# progESP.net
KiCad netlist of a schematic drawn in EAGLE
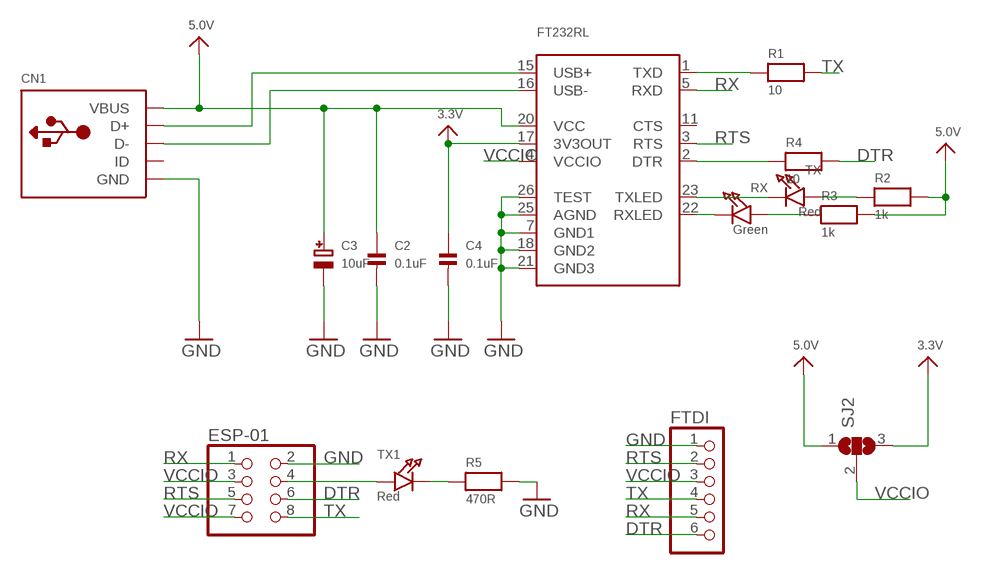
[diagram p0: schematic, sheet 1]

(export (version "E")
  (design (tool "Eeschema 10.0.6"))
  (components
    (comp (ref "C2")
      (value "0.1uF")
      (footprint "eagle-import:0805")
      (libsource (lib "eagle-import") (part "CAP_CERAMIC0805"))
    )
    (comp (ref "C3")
      (value "10uF")
      (footprint "eagle-import:EIA3216-18_A-R")
      (libsource (lib "eagle-import") (part "CAP_TANTALUMA/3216_REFLOW"))
    )
    (comp (ref "C4")
      (value "0.1uF")
      (footprint "eagle-import:0805")
      (libsource (lib "eagle-import") (part "CAP_CERAMIC0805"))
    )
    (comp (ref "CN1")
      (value "USBMINIB")
      (footprint "eagle-import:USB-MINIB")
      (libsource (lib "eagle-import") (part "USBMINIB"))
    )
    (comp (ref "ESP-01")
      (value "PINHD-2X4-ESP-01")
      (footprint "eagle-import:2X04")
      (libsource (lib "eagle-import") (part "PINHD-2X4-ESP-01"))
    )
    (comp (ref "FT232RL")
      (value "FT232RLSSOP28")
      (footprint "eagle-import:SSOP28DB")
      (libsource (lib "eagle-import") (part "FT232RLSSOP28"))
    )
    (comp (ref "FTDI")
      (value "PINHD-1X6")
      (footprint "eagle-import:1X06")
      (libsource (lib "eagle-import") (part "PINHD-1X6"))
    )
    (comp (ref "R1")
      (value "10")
      (footprint "eagle-import:0805")
      (libsource (lib "eagle-import") (part "RESISTOR0805"))
    )
    (comp (ref "R2")
      (value "1k")
      (footprint "eagle-import:0805")
      (libsource (lib "eagle-import") (part "RESISTOR0805"))
    )
    (comp (ref "R3")
      (value "1k")
      (footprint "eagle-import:0805")
      (libsource (lib "eagle-import") (part "RESISTOR0805"))
    )
    (comp (ref "R4")
      (value "10")
      (footprint "eagle-import:0805")
      (libsource (lib "eagle-import") (part "RESISTOR0805"))
    )
    (comp (ref "R5")
      (value "470R")
      (footprint "eagle-import:0805")
      (libsource (lib "eagle-import") (part "RESISTOR0805"))
    )
    (comp (ref "RX")
      (value "Green")
      (footprint "eagle-import:CHIPLED_0805")
      (libsource (lib "eagle-import") (part "LED0805"))
    )
    (comp (ref "SJ2")
      (value "SJ2W")
      (footprint "eagle-import:SJ_2")
      (libsource (lib "eagle-import") (part "SJ2W"))
    )
    (comp (ref "TX")
      (value "Red")
      (footprint "eagle-import:CHIPLED_0805")
      (libsource (lib "eagle-import") (part "LED0805"))
    )
    (comp (ref "TX1")
      (value "Red")
      (footprint "eagle-import:CHIPLED_0805")
      (libsource (lib "eagle-import") (part "LED0805"))
    )
  )
  (nets
    (net (code "1") (name "/DTR") (class "Default")
      (node (ref "ESP-01") (pin "6") (pinfunction "6_6") (pintype "passive"))
      (node (ref "FTDI") (pin "6") (pinfunction "6_6") (pintype "passive"))
      (node (ref "R4") (pin "2") (pinfunction "2_2") (pintype "passive"))
    )
    (net (code "2") (name "/RTS") (class "Default")
      (node (ref "ESP-01") (pin "5") (pinfunction "5_5") (pintype "passive"))
      (node (ref "FT232RL") (pin "3") (pinfunction "RTS_3") (pintype "bidirectional"))
      (node (ref "FTDI") (pin "2") (pinfunction "2_2") (pintype "passive"))
    )
    (net (code "3") (name "/RX") (class "Default")
      (node (ref "ESP-01") (pin "1") (pinfunction "1_1") (pintype "passive"))
      (node (ref "FT232RL") (pin "5") (pinfunction "RXD_5") (pintype "input"))
      (node (ref "FTDI") (pin "5") (pinfunction "5_5") (pintype "passive"))
    )
    (net (code "4") (name "/TX") (class "Default")
      (node (ref "ESP-01") (pin "8") (pinfunction "8_8") (pintype "passive"))
      (node (ref "FTDI") (pin "4") (pinfunction "4_4") (pintype "passive"))
      (node (ref "R1") (pin "2") (pinfunction "2_2") (pintype "passive"))
    )
    (net (code "5") (name "/VCCIO") (class "Default")
      (node (ref "ESP-01") (pin "3") (pinfunction "3_3") (pintype "passive"))
      (node (ref "ESP-01") (pin "7") (pinfunction "7_7") (pintype "passive"))
      (node (ref "FT232RL") (pin "4") (pinfunction "VCCIO_4") (pintype "power_in"))
      (node (ref "FTDI") (pin "3") (pinfunction "3_3") (pintype "passive"))
      (node (ref "SJ2") (pin "2") (pinfunction "2_2") (pintype "passive"))
    )
    (net (code "6") (name "3.3V") (class "Default")
      (node (ref "C4") (pin "1") (pinfunction "P$1_1") (pintype "passive"))
      (node (ref "FT232RL") (pin "17") (pinfunction "3V3OUT_17") (pintype "power_in"))
      (node (ref "SJ2") (pin "3") (pinfunction "3_3") (pintype "passive"))
    )
    (net (code "7") (name "5.0V") (class "Default")
      (node (ref "C2") (pin "1") (pinfunction "P$1_1") (pintype "passive"))
      (node (ref "C3") (pin "+") (pinfunction "+_+") (pintype "passive"))
      (node (ref "CN1") (pin "VBUS") (pinfunction "VBUS_VBUS") (pintype "power_in"))
      (node (ref "FT232RL") (pin "20") (pinfunction "VCC_20") (pintype "power_in"))
      (node (ref "R2") (pin "2") (pinfunction "2_2") (pintype "passive"))
      (node (ref "R3") (pin "2") (pinfunction "2_2") (pintype "passive"))
      (node (ref "SJ2") (pin "1") (pinfunction "1_1") (pintype "passive"))
    )
    (net (code "8") (name "GND") (class "Default")
      (node (ref "C2") (pin "2") (pinfunction "P$2_2") (pintype "passive"))
      (node (ref "C3") (pin "-") (pinfunction "-_-") (pintype "passive"))
      (node (ref "C4") (pin "2") (pinfunction "P$2_2") (pintype "passive"))
      (node (ref "CN1") (pin "GND") (pinfunction "GND_GND") (pintype "power_in"))
      (node (ref "ESP-01") (pin "2") (pinfunction "2_2") (pintype "passive"))
      (node (ref "FT232RL") (pin "18") (pinfunction "GND2_18") (pintype "power_in"))
      (node (ref "FT232RL") (pin "21") (pinfunction "GND3_21") (pintype "power_in"))
      (node (ref "FT232RL") (pin "25") (pinfunction "AGND_25") (pintype "power_in"))
      (node (ref "FT232RL") (pin "26") (pinfunction "TEST_26") (pintype "input"))
      (node (ref "FT232RL") (pin "7") (pinfunction "GND1_7") (pintype "power_in"))
      (node (ref "FTDI") (pin "1") (pinfunction "1_1") (pintype "passive"))
      (node (ref "R5") (pin "2") (pinfunction "2_2") (pintype "passive"))
    )
    (net (code "9") (name "Net-(ESP-01-Pad4)") (class "Default")
      (node (ref "ESP-01") (pin "4") (pinfunction "4_4") (pintype "passive"))
      (node (ref "TX1") (pin "A") (pinfunction "A_A") (pintype "passive"))
    )
    (net (code "10") (name "Net-(FT232RL-DTR)") (class "Default")
      (node (ref "FT232RL") (pin "2") (pinfunction "DTR_2") (pintype "bidirectional"))
      (node (ref "R4") (pin "1") (pinfunction "1_1") (pintype "passive"))
    )
    (net (code "11") (name "Net-(FT232RL-RXLED)") (class "Default")
      (node (ref "FT232RL") (pin "22") (pinfunction "RXLED_22") (pintype "bidirectional"))
      (node (ref "RX") (pin "C") (pinfunction "C_C") (pintype "passive"))
    )
    (net (code "12") (name "Net-(FT232RL-TXD)") (class "Default")
      (node (ref "FT232RL") (pin "1") (pinfunction "TXD_1") (pintype "output"))
      (node (ref "R1") (pin "1") (pinfunction "1_1") (pintype "passive"))
    )
    (net (code "13") (name "Net-(FT232RL-TXLED)") (class "Default")
      (node (ref "FT232RL") (pin "23") (pinfunction "TXLED_23") (pintype "bidirectional"))
      (node (ref "TX") (pin "C") (pinfunction "C_C") (pintype "passive"))
    )
    (net (code "14") (name "Net-(FT232RL-USB+)") (class "Default")
      (node (ref "CN1") (pin "D+") (pinfunction "D+_D+") (pintype "bidirectional"))
      (node (ref "FT232RL") (pin "15") (pinfunction "USB+_15") (pintype "bidirectional"))
    )
    (net (code "15") (name "Net-(FT232RL-USB-)") (class "Default")
      (node (ref "CN1") (pin "D-") (pinfunction "D-_D-") (pintype "bidirectional"))
      (node (ref "FT232RL") (pin "16") (pinfunction "USB-_16") (pintype "bidirectional"))
    )
    (net (code "16") (name "Net-(R2-Pad1)") (class "Default")
      (node (ref "R2") (pin "1") (pinfunction "1_1") (pintype "passive"))
      (node (ref "TX") (pin "A") (pinfunction "A_A") (pintype "passive"))
    )
    (net (code "17") (name "Net-(R3-Pad1)") (class "Default")
      (node (ref "R3") (pin "1") (pinfunction "1_1") (pintype "passive"))
      (node (ref "RX") (pin "A") (pinfunction "A_A") (pintype "passive"))
    )
    (net (code "18") (name "Net-(R5-Pad1)") (class "Default")
      (node (ref "R5") (pin "1") (pinfunction "1_1") (pintype "passive"))
      (node (ref "TX1") (pin "C") (pinfunction "C_C") (pintype "passive"))
    )
    (net (code "19") (name "unconnected-(CN1-PadID)") (class "Default")
      (node (ref "CN1") (pin "ID") (pinfunction "ID_ID") (pintype "bidirectional"))
    )
    (net (code "20") (name "unconnected-(FT232RL-CTS-Pad11)") (class "Default")
      (node (ref "FT232RL") (pin "11") (pinfunction "CTS_11") (pintype "bidirectional"))
    )
  )
)
